# gps-breakout-mk-1_1.net
KiCad netlist of a schematic drawn in EAGLE
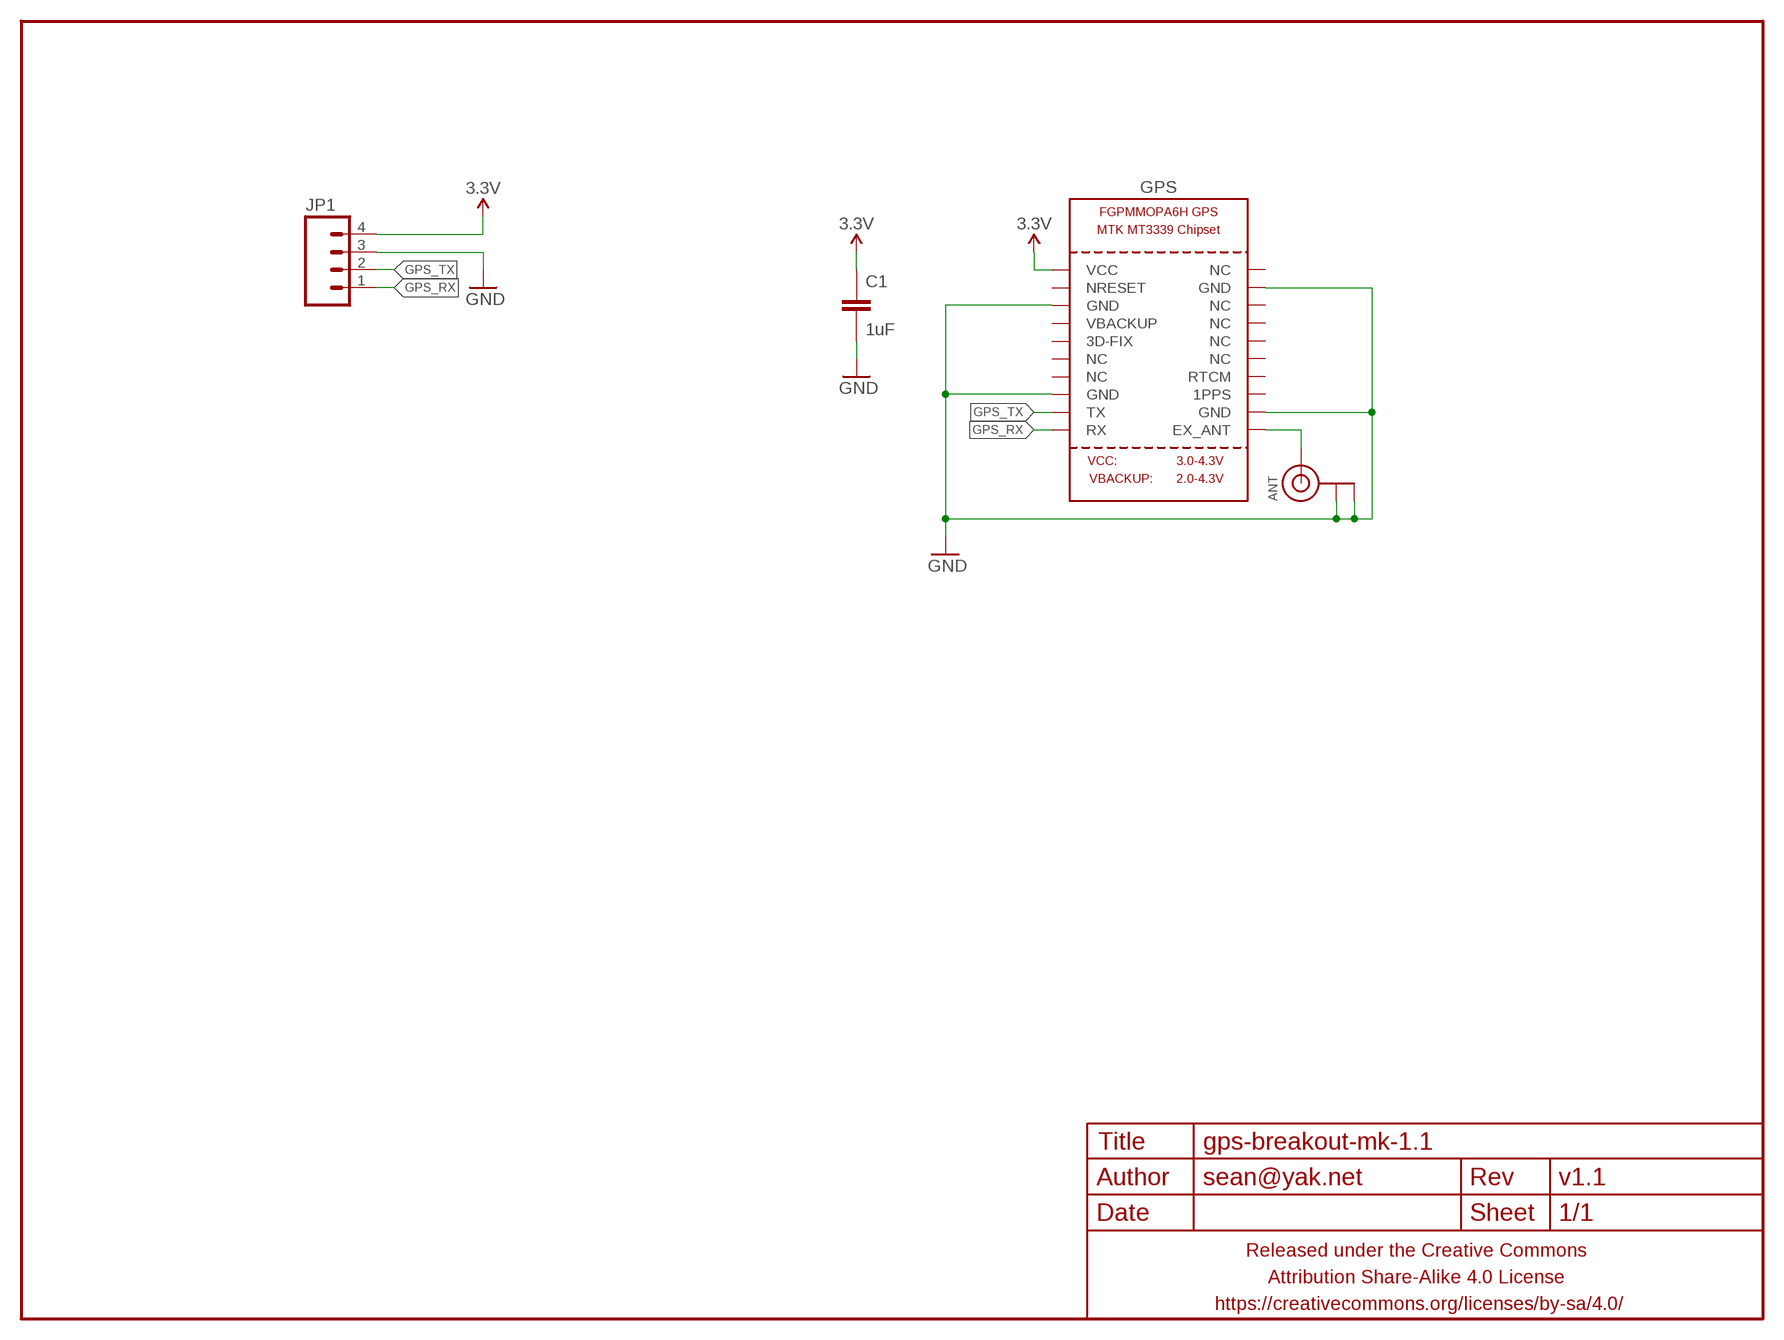
[diagram p0: schematic, sheet 1]

(export (version "E")
  (design (tool "Eeschema 10.0.6"))
  (components
    (comp (ref "ANT")
      (value "ANTENNA_U.FL")
      (footprint "eagle-import:U.FL")
      (libsource (lib "eagle-import") (part "ANTENNA_U.FL"))
    )
    (comp (ref "C1")
      (value "1uF")
      (footprint "eagle-import:C0402")
      (libsource (lib "eagle-import") (part "CAPACITOR-CERAMICC0402"))
    )
    (comp (ref "FRAME1")
      (value "FRAME-LETTERNO_PACKAGE")
      (footprint "eagle-import:DUMMY")
      (fields (field (name "DESIGNER") "sean@yak.net") (field (name "VERSION") "v1.1"))
      (libsource (lib "eagle-import") (part "FRAME-LETTERNO_PACKAGE"))
    )
    (comp (ref "GPS")
      (value "GPS_FGPMMOPA6H")
      (footprint "eagle-import:FGPMMOPA6H")
      (libsource (lib "eagle-import") (part "GPS_FGPMMOPA6H"))
    )
    (comp (ref "JP1")
      (value "M04PTH-NS-CENTERED")
      (footprint "eagle-import:1X04-PTH-VERT-NS-CENTERED")
      (libsource (lib "eagle-import") (part "M04PTH-NS-CENTERED"))
    )
  )
  (nets
    (net (code "1") (name "3.3V") (class "Default")
      (node (ref "C1") (pin "1") (pinfunction "1_1") (pintype "passive"))
      (node (ref "GPS") (pin "P$1") (pinfunction "VCC_P$1") (pintype "bidirectional"))
      (node (ref "JP1") (pin "4") (pinfunction "4_4") (pintype "passive"))
    )
    (net (code "2") (name "GND") (class "Default")
      (node (ref "ANT") (pin "1") (pinfunction "GND_1") (pintype "passive"))
      (node (ref "ANT") (pin "2") (pinfunction "GND_2") (pintype "passive"))
      (node (ref "C1") (pin "2") (pinfunction "2_2") (pintype "passive"))
      (node (ref "GPS") (pin "P$12") (pinfunction "GND_P$12") (pintype "bidirectional"))
      (node (ref "GPS") (pin "P$19") (pinfunction "GND_P$19") (pintype "bidirectional"))
      (node (ref "GPS") (pin "P$3") (pinfunction "GND_P$3") (pintype "bidirectional"))
      (node (ref "GPS") (pin "P$8") (pinfunction "GND_P$8") (pintype "bidirectional"))
      (node (ref "JP1") (pin "3") (pinfunction "3_3") (pintype "passive"))
    )
    (net (code "3") (name "GPS_RX") (class "Default")
      (node (ref "GPS") (pin "P$10") (pinfunction "RX_P$10") (pintype "bidirectional"))
      (node (ref "JP1") (pin "1") (pinfunction "1_1") (pintype "passive"))
    )
    (net (code "4") (name "GPS_TX") (class "Default")
      (node (ref "GPS") (pin "P$9") (pinfunction "TX_P$9") (pintype "bidirectional"))
      (node (ref "JP1") (pin "2") (pinfunction "2_2") (pintype "passive"))
    )
    (net (code "5") (name "Net-(ANT-SIGNAL)") (class "Default")
      (node (ref "ANT") (pin "3") (pinfunction "SIGNAL_3") (pintype "passive"))
      (node (ref "GPS") (pin "P$11") (pinfunction "EX_ANT_P$11") (pintype "bidirectional"))
    )
    (net (code "6") (name "unconnected-(GPS-1PPS-PadP$13)") (class "Default")
      (node (ref "GPS") (pin "P$13") (pinfunction "1PPS_P$13") (pintype "bidirectional"))
    )
    (net (code "7") (name "unconnected-(GPS-3D-FIX-PadP$5)") (class "Default")
      (node (ref "GPS") (pin "P$5") (pinfunction "3D-FIX_P$5") (pintype "bidirectional"))
    )
    (net (code "8") (name "unconnected-(GPS-NC-PadP$6)") (class "Default")
      (node (ref "GPS") (pin "P$6") (pinfunction "NC_P$6") (pintype "bidirectional"))
    )
    (net (code "9") (name "unconnected-(GPS-NC-PadP$7)") (class "Default")
      (node (ref "GPS") (pin "P$7") (pinfunction "NC_P$7") (pintype "bidirectional"))
    )
    (net (code "10") (name "unconnected-(GPS-NC-PadP$15)") (class "Default")
      (node (ref "GPS") (pin "P$15") (pinfunction "NC_P$15") (pintype "bidirectional"))
    )
    (net (code "11") (name "unconnected-(GPS-NC-PadP$16)") (class "Default")
      (node (ref "GPS") (pin "P$16") (pinfunction "NC_P$16") (pintype "bidirectional"))
    )
    (net (code "12") (name "unconnected-(GPS-NC-PadP$17)") (class "Default")
      (node (ref "GPS") (pin "P$17") (pinfunction "NC_P$17") (pintype "bidirectional"))
    )
    (net (code "13") (name "unconnected-(GPS-NC-PadP$18)") (class "Default")
      (node (ref "GPS") (pin "P$18") (pinfunction "NC_P$18") (pintype "bidirectional"))
    )
    (net (code "14") (name "unconnected-(GPS-NC-PadP$20)") (class "Default")
      (node (ref "GPS") (pin "P$20") (pinfunction "NC_P$20") (pintype "bidirectional"))
    )
    (net (code "15") (name "unconnected-(GPS-NRESET-PadP$2)") (class "Default")
      (node (ref "GPS") (pin "P$2") (pinfunction "NRESET_P$2") (pintype "bidirectional"))
    )
    (net (code "16") (name "unconnected-(GPS-RTCM-PadP$14)") (class "Default")
      (node (ref "GPS") (pin "P$14") (pinfunction "RTCM_P$14") (pintype "bidirectional"))
    )
    (net (code "17") (name "unconnected-(GPS-VBACKUP-PadP$4)") (class "Default")
      (node (ref "GPS") (pin "P$4") (pinfunction "VBACKUP_P$4") (pintype "bidirectional"))
    )
  )
)
